# panel_controller_rev_c.net
KiCad netlist of a schematic drawn in EAGLE
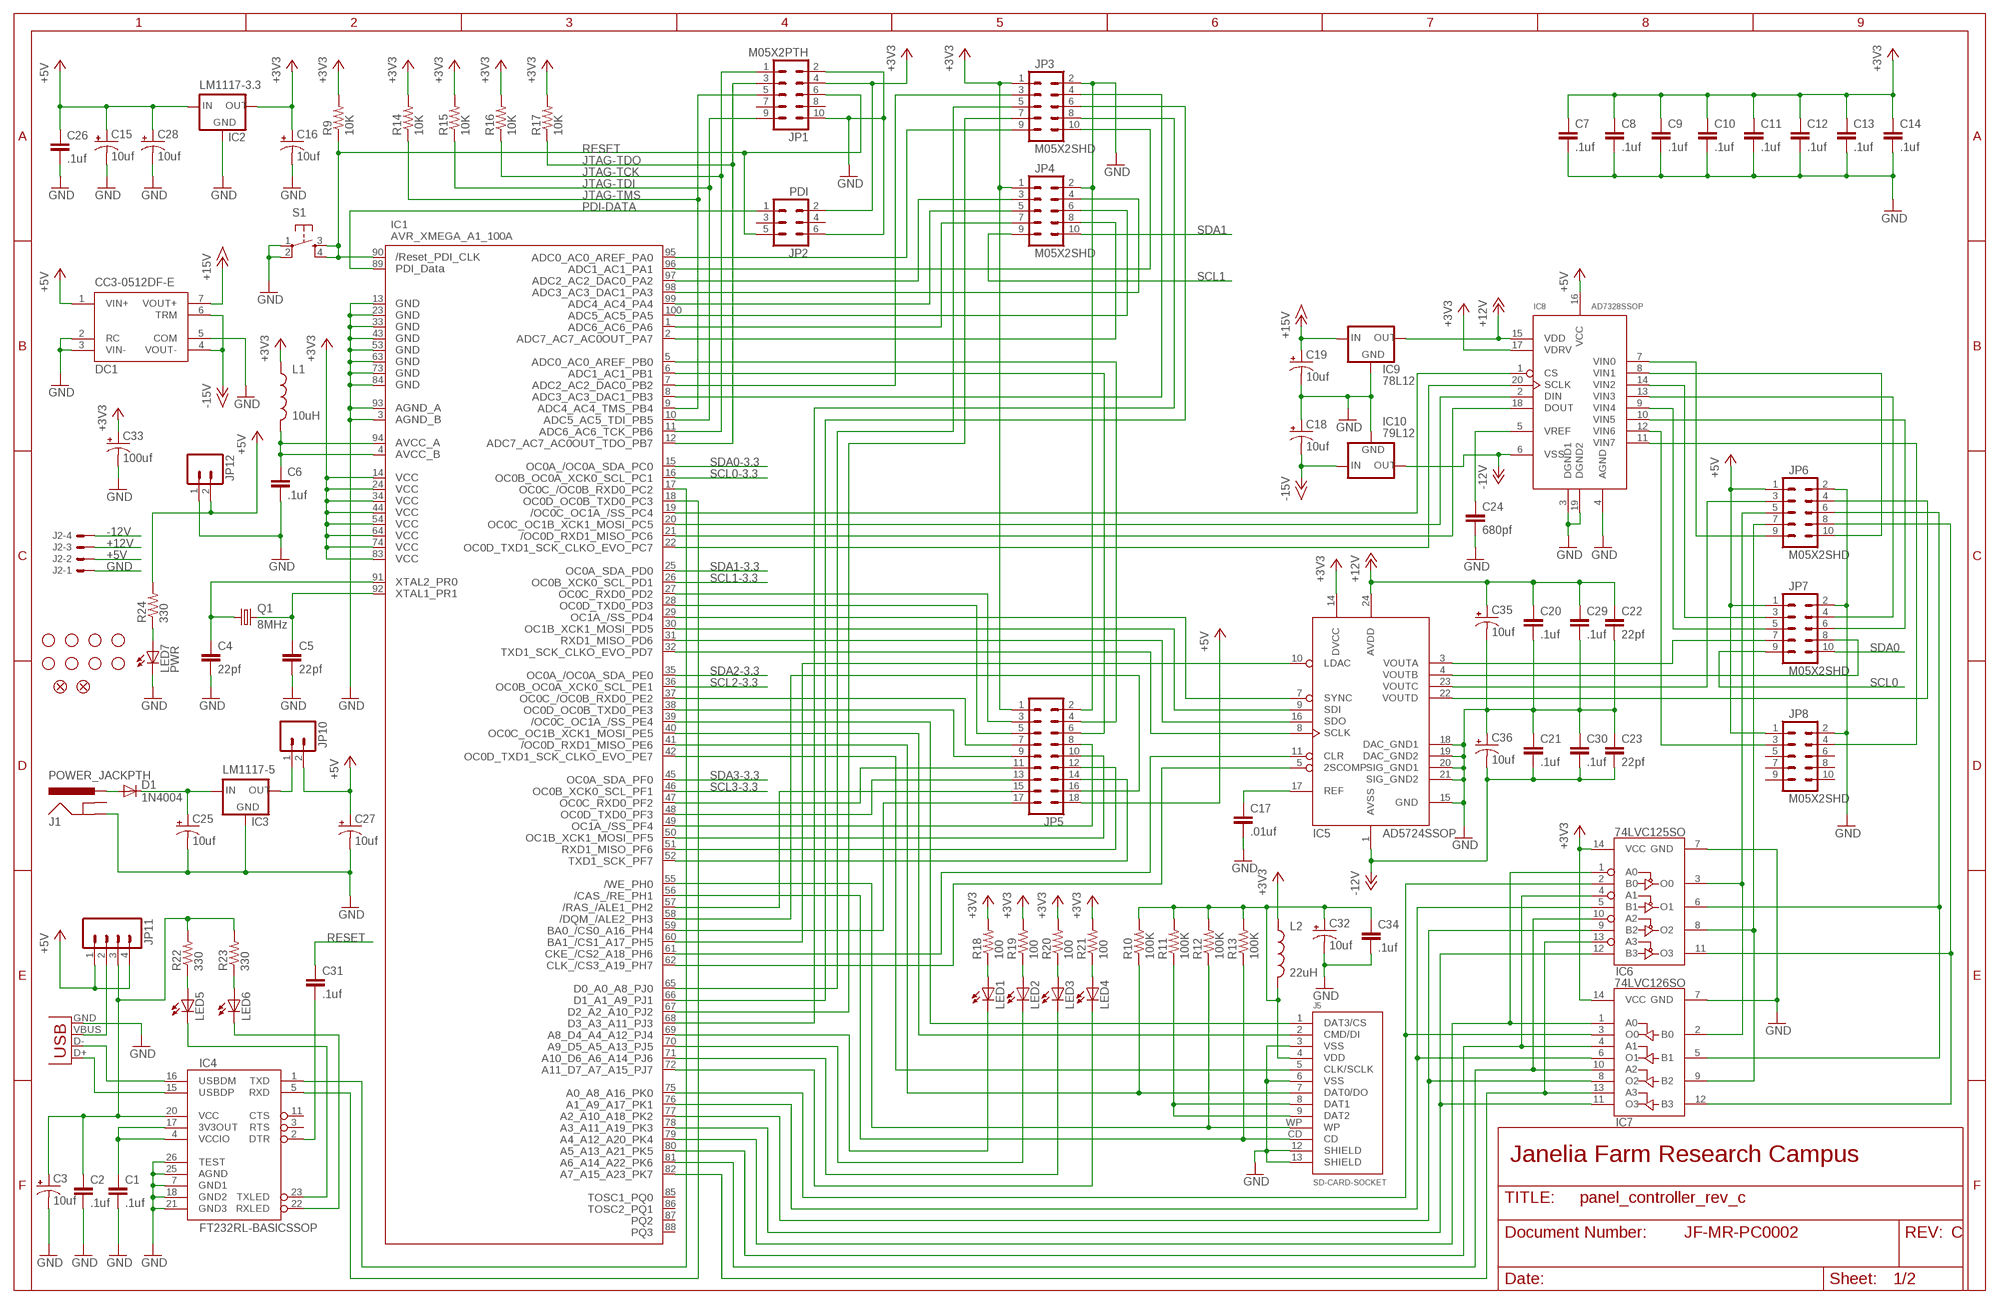
[diagram p0: schematic, sheet 1]
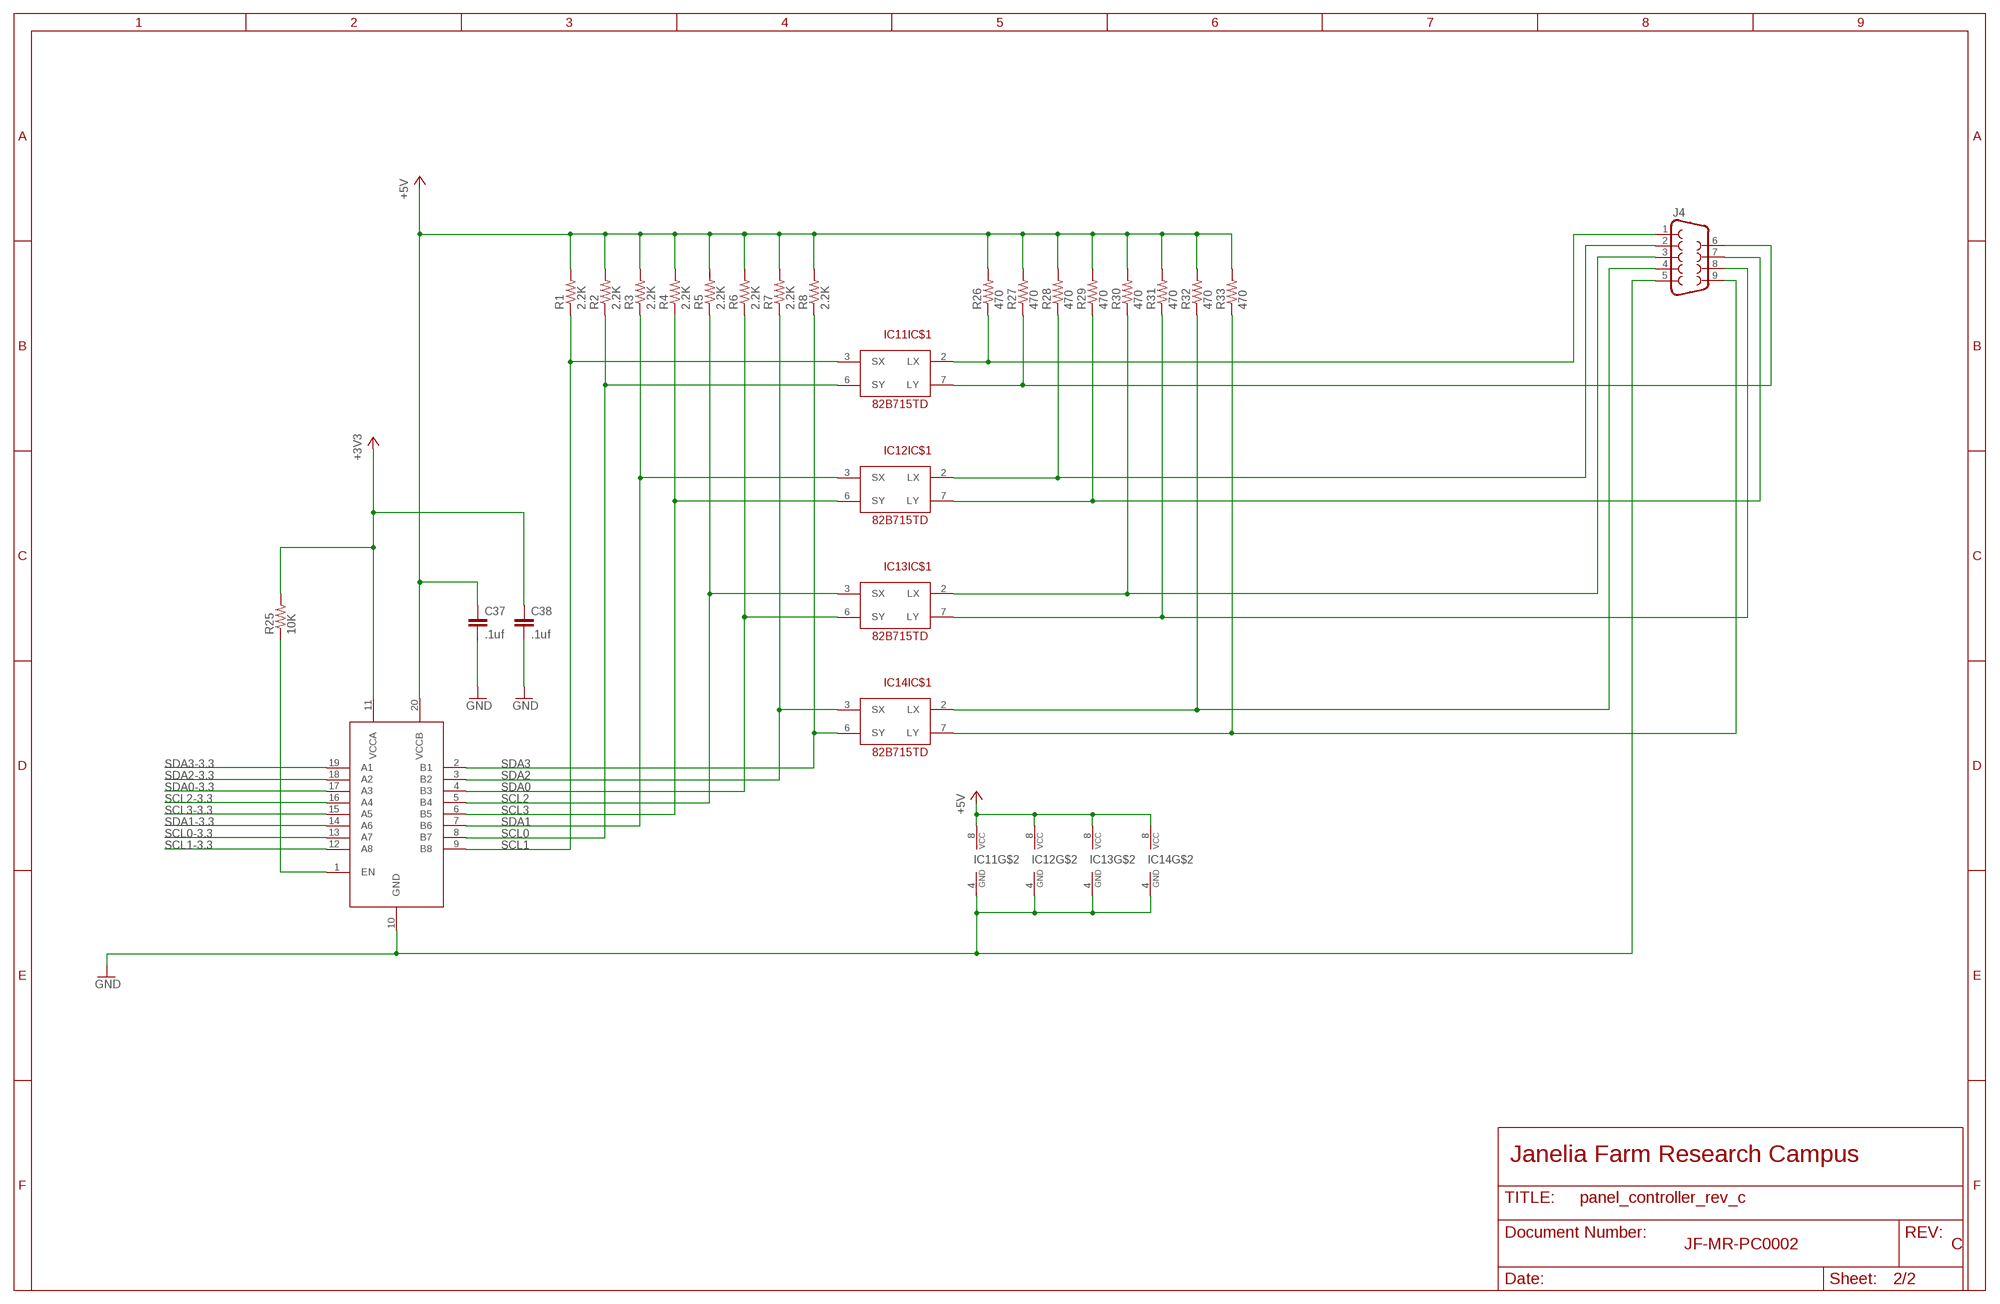
[diagram p1: schematic, sheet 2]

(export (version "E")
  (design (tool "Eeschema 10.0.6"))
  (components
    (comp (ref "C1")
      (value ".1uf")
      (footprint "eagle-import:0603")
      (libsource (lib "eagle-import") (part "CAP0603"))
    )
    (comp (ref "C2")
      (value ".1uf")
      (footprint "eagle-import:0603")
      (libsource (lib "eagle-import") (part "CAP0603"))
    )
    (comp (ref "C3")
      (value "10uf")
      (footprint "eagle-import:EIA3216")
      (libsource (lib "eagle-import") (part "CAP_POL1206"))
    )
    (comp (ref "C4")
      (value "22pf")
      (footprint "eagle-import:0603")
      (libsource (lib "eagle-import") (part "CAP0603"))
    )
    (comp (ref "C5")
      (value "22pf")
      (footprint "eagle-import:0603")
      (libsource (lib "eagle-import") (part "CAP0603"))
    )
    (comp (ref "C6")
      (value ".1uf")
      (footprint "eagle-import:0603")
      (libsource (lib "eagle-import") (part "CAP0603"))
    )
    (comp (ref "C7")
      (value ".1uf")
      (footprint "eagle-import:0603")
      (libsource (lib "eagle-import") (part "CAP0603"))
    )
    (comp (ref "C8")
      (value ".1uf")
      (footprint "eagle-import:0603")
      (libsource (lib "eagle-import") (part "CAP0603"))
    )
    (comp (ref "C9")
      (value ".1uf")
      (footprint "eagle-import:0603")
      (libsource (lib "eagle-import") (part "CAP0603"))
    )
    (comp (ref "C10")
      (value ".1uf")
      (footprint "eagle-import:0603")
      (libsource (lib "eagle-import") (part "CAP0603"))
    )
    (comp (ref "C11")
      (value ".1uf")
      (footprint "eagle-import:0603")
      (libsource (lib "eagle-import") (part "CAP0603"))
    )
    (comp (ref "C12")
      (value ".1uf")
      (footprint "eagle-import:0603")
      (libsource (lib "eagle-import") (part "CAP0603"))
    )
    (comp (ref "C13")
      (value ".1uf")
      (footprint "eagle-import:0603")
      (libsource (lib "eagle-import") (part "CAP0603"))
    )
    (comp (ref "C14")
      (value ".1uf")
      (footprint "eagle-import:0603")
      (libsource (lib "eagle-import") (part "CAP0603"))
    )
    (comp (ref "C15")
      (value "10uf")
      (footprint "eagle-import:EIA3216")
      (libsource (lib "eagle-import") (part "CAP_POL1206"))
    )
    (comp (ref "C16")
      (value "10uf")
      (footprint "eagle-import:EIA3216")
      (libsource (lib "eagle-import") (part "CAP_POL1206"))
    )
    (comp (ref "C17")
      (value ".01uf")
      (footprint "eagle-import:0603")
      (libsource (lib "eagle-import") (part "CAP0603"))
    )
    (comp (ref "C18")
      (value "10uf")
      (footprint "eagle-import:EIA3216")
      (libsource (lib "eagle-import") (part "CAP_POL1206"))
    )
    (comp (ref "C19")
      (value "10uf")
      (footprint "eagle-import:EIA3216")
      (libsource (lib "eagle-import") (part "CAP_POL1206"))
    )
    (comp (ref "C20")
      (value ".1uf")
      (footprint "eagle-import:0603")
      (libsource (lib "eagle-import") (part "CAP0603"))
    )
    (comp (ref "C21")
      (value ".1uf")
      (footprint "eagle-import:0603")
      (libsource (lib "eagle-import") (part "CAP0603"))
    )
    (comp (ref "C22")
      (value "22pf")
      (footprint "eagle-import:0603")
      (libsource (lib "eagle-import") (part "CAP0603"))
    )
    (comp (ref "C23")
      (value "22pf")
      (footprint "eagle-import:0603")
      (libsource (lib "eagle-import") (part "CAP0603"))
    )
    (comp (ref "C24")
      (value "680pf")
      (footprint "eagle-import:0603")
      (libsource (lib "eagle-import") (part "CAP0603"))
    )
    (comp (ref "C25")
      (value "10uf")
      (footprint "eagle-import:EIA3216")
      (libsource (lib "eagle-import") (part "CAP_POL1206"))
    )
    (comp (ref "C26")
      (value ".1uf")
      (footprint "eagle-import:0603")
      (libsource (lib "eagle-import") (part "CAP0603"))
    )
    (comp (ref "C27")
      (value "10uf")
      (footprint "eagle-import:EIA3216")
      (libsource (lib "eagle-import") (part "CAP_POL1206"))
    )
    (comp (ref "C28")
      (value "10uf")
      (footprint "eagle-import:EIA3216")
      (libsource (lib "eagle-import") (part "CAP_POL1206"))
    )
    (comp (ref "C29")
      (value ".1uf")
      (footprint "eagle-import:0603")
      (libsource (lib "eagle-import") (part "CAP0603"))
    )
    (comp (ref "C30")
      (value ".1uf")
      (footprint "eagle-import:0603")
      (libsource (lib "eagle-import") (part "CAP0603"))
    )
    (comp (ref "C31")
      (value ".1uf")
      (footprint "eagle-import:0603")
      (libsource (lib "eagle-import") (part "CAP0603"))
    )
    (comp (ref "C32")
      (value "10uf")
      (footprint "eagle-import:EIA3216")
      (libsource (lib "eagle-import") (part "CAP_POL1206"))
    )
    (comp (ref "C33")
      (value "100uf")
      (footprint "eagle-import:PANASONIC_E")
      (libsource (lib "eagle-import") (part "CAP_POLE"))
    )
    (comp (ref "C34")
      (value ".1uf")
      (footprint "eagle-import:0603")
      (libsource (lib "eagle-import") (part "CAP0603"))
    )
    (comp (ref "C35")
      (value "10uf")
      (footprint "eagle-import:EIA3216")
      (libsource (lib "eagle-import") (part "CAP_POL1206"))
    )
    (comp (ref "C36")
      (value "10uf")
      (footprint "eagle-import:EIA3216")
      (libsource (lib "eagle-import") (part "CAP_POL1206"))
    )
    (comp (ref "D1")
      (value "1N4004")
      (footprint "eagle-import:DO41-10")
      (libsource (lib "eagle-import") (part "1N4004"))
    )
    (comp (ref "DC1")
      (value "CC3-0512DF-E")
      (footprint "eagle-import:CC3-TH")
      (libsource (lib "eagle-import") (part "CC3-0512DF-E"))
    )
    (comp (ref "IC1")
      (value "AVR_XMEGA_A1_100A")
      (footprint "eagle-import:TQFP100")
      (libsource (lib "eagle-import") (part "AVR_XMEGA_A1_100A"))
    )
    (comp (ref "IC2")
      (value "LM1117-3.3")
      (footprint "eagle-import:SOT223")
      (libsource (lib "eagle-import") (part "V_REG_LM1117SOT223"))
    )
    (comp (ref "IC3")
      (value "LM1117-5")
      (footprint "eagle-import:SOT223")
      (libsource (lib "eagle-import") (part "V_REG_LM1117SOT223"))
    )
    (comp (ref "IC4")
      (value "FT232RL-BASICSSOP")
      (footprint "eagle-import:SSOP28DB")
      (libsource (lib "eagle-import") (part "FT232RL-BASICSSOP"))
    )
    (comp (ref "IC5")
      (value "AD5724SSOP")
      (footprint "eagle-import:TSSOP24")
      (libsource (lib "eagle-import") (part "AD5724SSOP"))
    )
    (comp (ref "IC6")
      (value "74LVC125SO")
      (footprint "eagle-import:SO014")
      (libsource (lib "eagle-import") (part "74LVC125SO"))
    )
    (comp (ref "IC7")
      (value "74LVC126SO")
      (footprint "eagle-import:SO014")
      (libsource (lib "eagle-import") (part "74LVC126SO"))
    )
    (comp (ref "IC8")
      (value "AD7328SSOP")
      (footprint "eagle-import:TSSOP20")
      (libsource (lib "eagle-import") (part "AD7328SSOP"))
    )
    (comp (ref "IC9")
      (value "78L12")
      (footprint "eagle-import:SOT89")
      (libsource (lib "eagle-import") (part "78LXXSOT89"))
    )
    (comp (ref "IC10")
      (value "79L12")
      (footprint "eagle-import:SOT89")
      (libsource (lib "eagle-import") (part "79LXXSOT89"))
    )
    (comp (ref "J1")
      (value "POWER_JACKPTH")
      (footprint "eagle-import:POWER_JACK_PTH")
      (libsource (lib "eagle-import") (part "POWER_JACKPTH"))
    )
    (comp (ref "J2")
      (value "KK-156-4")
      (footprint "eagle-import:KK-156-4")
      (libsource (lib "eagle-import") (part "KK-156-4"))
    )
    (comp (ref "J3")
      (value "USBPTH")
      (footprint "eagle-import:USB-B-PTH")
      (libsource (lib "eagle-import") (part "USBPTH"))
    )
    (comp (ref "J5")
      (value "SD-CARD-SOCKET")
      (footprint "eagle-import:SD-MMC_SOCKET-3M")
      (libsource (lib "eagle-import") (part "SD-CARD-SOCKET"))
    )
    (comp (ref "JP1")
      (value "M05X2PTH")
      (footprint "eagle-import:MA05-2")
      (libsource (lib "eagle-import") (part "MA05-2"))
    )
    (comp (ref "JP2")
      (value "PDI")
      (footprint "eagle-import:MA03-2")
      (libsource (lib "eagle-import") (part "MA03-2"))
    )
    (comp (ref "JP3")
      (value "M05X2SHD")
      (footprint "eagle-import:2X5-SHROUDED")
      (libsource (lib "eagle-import") (part "M05X2SHD"))
    )
    (comp (ref "JP4")
      (value "M05X2SHD")
      (footprint "eagle-import:2X5-SHROUDED")
      (libsource (lib "eagle-import") (part "M05X2SHD"))
    )
    (comp (ref "JP5")
      (value "MA09-2")
      (footprint "eagle-import:MA09-2")
      (libsource (lib "eagle-import") (part "MA09-2"))
    )
    (comp (ref "JP6")
      (value "M05X2SHD")
      (footprint "eagle-import:2X5-SHROUDED")
      (libsource (lib "eagle-import") (part "M05X2SHD"))
    )
    (comp (ref "JP7")
      (value "M05X2SHD")
      (footprint "eagle-import:2X5-SHROUDED")
      (libsource (lib "eagle-import") (part "M05X2SHD"))
    )
    (comp (ref "JP8")
      (value "M05X2SHD")
      (footprint "eagle-import:2X5-SHROUDED")
      (libsource (lib "eagle-import") (part "M05X2SHD"))
    )
    (comp (ref "JP10")
      (value "M02PTH")
      (footprint "eagle-import:1X02")
      (libsource (lib "eagle-import") (part "M02PTH"))
    )
    (comp (ref "JP11")
      (value "M04PTH")
      (footprint "eagle-import:1X04")
      (libsource (lib "eagle-import") (part "M04PTH"))
    )
    (comp (ref "JP12")
      (value "M02PTH")
      (footprint "eagle-import:1X02")
      (libsource (lib "eagle-import") (part "M02PTH"))
    )
    (comp (ref "L1")
      (value "10uH")
      (footprint "eagle-import:0805")
      (libsource (lib "eagle-import") (part "INDUCTOR0805"))
    )
    (comp (ref "L2")
      (value "22uH")
      (footprint "eagle-import:0805")
      (libsource (lib "eagle-import") (part "INDUCTOR0805"))
    )
    (comp (ref "LED1")
      (value "LED3MM")
      (footprint "eagle-import:LED3MM")
      (libsource (lib "eagle-import") (part "LED3MM"))
    )
    (comp (ref "LED2")
      (value "LED3MM")
      (footprint "eagle-import:LED3MM")
      (libsource (lib "eagle-import") (part "LED3MM"))
    )
    (comp (ref "LED3")
      (value "LED3MM")
      (footprint "eagle-import:LED3MM")
      (libsource (lib "eagle-import") (part "LED3MM"))
    )
    (comp (ref "LED4")
      (value "LED3MM")
      (footprint "eagle-import:LED3MM")
      (libsource (lib "eagle-import") (part "LED3MM"))
    )
    (comp (ref "LED5")
      (value "LED3MM")
      (footprint "eagle-import:LED3MM")
      (libsource (lib "eagle-import") (part "LED3MM"))
    )
    (comp (ref "LED6")
      (value "LED3MM")
      (footprint "eagle-import:LED3MM")
      (libsource (lib "eagle-import") (part "LED3MM"))
    )
    (comp (ref "LED7")
      (value "PWR")
      (footprint "eagle-import:LED3MM")
      (libsource (lib "eagle-import") (part "LED3MM"))
    )
    (comp (ref "Q1")
      (value "8MHz")
      (footprint "eagle-import:HC49UP")
      (libsource (lib "eagle-import") (part "CRYSTALSMD"))
    )
    (comp (ref "R9")
      (value "10K")
      (footprint "eagle-import:0603")
      (libsource (lib "eagle-import") (part "RESISTOR0603"))
    )
    (comp (ref "R10")
      (value "100K")
      (footprint "eagle-import:0603")
      (libsource (lib "eagle-import") (part "RESISTOR0603"))
    )
    (comp (ref "R11")
      (value "100K")
      (footprint "eagle-import:0603")
      (libsource (lib "eagle-import") (part "RESISTOR0603"))
    )
    (comp (ref "R12")
      (value "100K")
      (footprint "eagle-import:0603")
      (libsource (lib "eagle-import") (part "RESISTOR0603"))
    )
    (comp (ref "R13")
      (value "100K")
      (footprint "eagle-import:0603")
      (libsource (lib "eagle-import") (part "RESISTOR0603"))
    )
    (comp (ref "R14")
      (value "10K")
      (footprint "eagle-import:0603")
      (libsource (lib "eagle-import") (part "RESISTOR0603"))
    )
    (comp (ref "R15")
      (value "10K")
      (footprint "eagle-import:0603")
      (libsource (lib "eagle-import") (part "RESISTOR0603"))
    )
    (comp (ref "R16")
      (value "10K")
      (footprint "eagle-import:0603")
      (libsource (lib "eagle-import") (part "RESISTOR0603"))
    )
    (comp (ref "R17")
      (value "10K")
      (footprint "eagle-import:0603")
      (libsource (lib "eagle-import") (part "RESISTOR0603"))
    )
    (comp (ref "R18")
      (value "100")
      (footprint "eagle-import:0603")
      (libsource (lib "eagle-import") (part "RESISTOR0603"))
    )
    (comp (ref "R19")
      (value "100")
      (footprint "eagle-import:0603")
      (libsource (lib "eagle-import") (part "RESISTOR0603"))
    )
    (comp (ref "R20")
      (value "100")
      (footprint "eagle-import:0603")
      (libsource (lib "eagle-import") (part "RESISTOR0603"))
    )
    (comp (ref "R21")
      (value "100")
      (footprint "eagle-import:0603")
      (libsource (lib "eagle-import") (part "RESISTOR0603"))
    )
    (comp (ref "R22")
      (value "330")
      (footprint "eagle-import:0603")
      (libsource (lib "eagle-import") (part "RESISTOR0603"))
    )
    (comp (ref "R23")
      (value "330")
      (footprint "eagle-import:0603")
      (libsource (lib "eagle-import") (part "RESISTOR0603"))
    )
    (comp (ref "R24")
      (value "330")
      (footprint "eagle-import:0603")
      (libsource (lib "eagle-import") (part "RESISTOR0603"))
    )
    (comp (ref "S1")
      (value "TAC_SWITCHB3S-1000")
      (footprint "eagle-import:OMRON")
      (libsource (lib "eagle-import") (part "TAC_SWITCHB3S-1000"))
    )
    (comp (ref "U$1")
      (value "FIDUCIAL1X2")
      (footprint "eagle-import:FIDUCIAL-1X2")
      (libsource (lib "eagle-import") (part "FIDUCIAL1X2"))
    )
    (comp (ref "U$2")
      (value "FIDUCIAL1X2")
      (footprint "eagle-import:FIDUCIAL-1X2")
      (libsource (lib "eagle-import") (part "FIDUCIAL1X2"))
    )
    (comp (ref "U$3")
      (value "STAND-OFF")
      (footprint "eagle-import:STAND-OFF")
      (libsource (lib "eagle-import") (part "STAND-OFF"))
    )
    (comp (ref "U$4")
      (value "STAND-OFF")
      (footprint "eagle-import:STAND-OFF")
      (libsource (lib "eagle-import") (part "STAND-OFF"))
    )
    (comp (ref "U$5")
      (value "STAND-OFF")
      (footprint "eagle-import:STAND-OFF")
      (libsource (lib "eagle-import") (part "STAND-OFF"))
    )
    (comp (ref "U$6")
      (value "STAND-OFF")
      (footprint "eagle-import:STAND-OFF")
      (libsource (lib "eagle-import") (part "STAND-OFF"))
    )
    (comp (ref "U$7")
      (value "STAND-OFF")
      (footprint "eagle-import:STAND-OFF")
      (libsource (lib "eagle-import") (part "STAND-OFF"))
    )
    (comp (ref "U$8")
      (value "STAND-OFF")
      (footprint "eagle-import:STAND-OFF")
      (libsource (lib "eagle-import") (part "STAND-OFF"))
    )
    (comp (ref "U$9")
      (value "STAND-OFF")
      (footprint "eagle-import:STAND-OFF")
      (libsource (lib "eagle-import") (part "STAND-OFF"))
    )
    (comp (ref "U$10")
      (value "STAND-OFF")
      (footprint "eagle-import:STAND-OFF")
      (libsource (lib "eagle-import") (part "STAND-OFF"))
    )
    (comp (ref "C37")
      (value ".1uf")
      (footprint "eagle-import:0603")
      (libsource (lib "eagle-import") (part "CAP0603"))
    )
    (comp (ref "C38")
      (value ".1uf")
      (footprint "eagle-import:0603")
      (libsource (lib "eagle-import") (part "CAP0603"))
    )
    (comp (ref "IC11")
      (value "82B715TD")
      (footprint "eagle-import:SO08")
      (libsource (lib "eagle-import") (part "82B715TD"))
    )
    (comp (ref "IC12")
      (value "82B715TD")
      (footprint "eagle-import:SO08")
      (libsource (lib "eagle-import") (part "82B715TD"))
    )
    (comp (ref "IC13")
      (value "82B715TD")
      (footprint "eagle-import:SO08")
      (libsource (lib "eagle-import") (part "82B715TD"))
    )
    (comp (ref "IC14")
      (value "82B715TD")
      (footprint "eagle-import:SO08")
      (libsource (lib "eagle-import") (part "82B715TD"))
    )
    (comp (ref "IC15")
      (value "PCA9519")
      (footprint "eagle-import:TSSOP20")
      (libsource (lib "eagle-import") (part "PCA9519"))
    )
    (comp (ref "J4")
      (value "DB9")
      (footprint "eagle-import:DB9")
      (libsource (lib "eagle-import") (part "DB9"))
    )
    (comp (ref "R1")
      (value "2.2K")
      (footprint "eagle-import:0603")
      (libsource (lib "eagle-import") (part "RESISTOR0603"))
    )
    (comp (ref "R2")
      (value "2.2K")
      (footprint "eagle-import:0603")
      (libsource (lib "eagle-import") (part "RESISTOR0603"))
    )
    (comp (ref "R3")
      (value "2.2K")
      (footprint "eagle-import:0603")
      (libsource (lib "eagle-import") (part "RESISTOR0603"))
    )
    (comp (ref "R4")
      (value "2.2K")
      (footprint "eagle-import:0603")
      (libsource (lib "eagle-import") (part "RESISTOR0603"))
    )
    (comp (ref "R5")
      (value "2.2K")
      (footprint "eagle-import:0603")
      (libsource (lib "eagle-import") (part "RESISTOR0603"))
    )
    (comp (ref "R6")
      (value "2.2K")
      (footprint "eagle-import:0603")
      (libsource (lib "eagle-import") (part "RESISTOR0603"))
    )
    (comp (ref "R7")
      (value "2.2K")
      (footprint "eagle-import:0603")
      (libsource (lib "eagle-import") (part "RESISTOR0603"))
    )
    (comp (ref "R8")
      (value "2.2K")
      (footprint "eagle-import:0603")
      (libsource (lib "eagle-import") (part "RESISTOR0603"))
    )
    (comp (ref "R25")
      (value "10K")
      (footprint "eagle-import:0603")
      (libsource (lib "eagle-import") (part "RESISTOR0603"))
    )
    (comp (ref "R26")
      (value "470")
      (footprint "eagle-import:0603")
      (libsource (lib "eagle-import") (part "RESISTOR0603"))
    )
    (comp (ref "R27")
      (value "470")
      (footprint "eagle-import:0603")
      (libsource (lib "eagle-import") (part "RESISTOR0603"))
    )
    (comp (ref "R28")
      (value "470")
      (footprint "eagle-import:0603")
      (libsource (lib "eagle-import") (part "RESISTOR0603"))
    )
    (comp (ref "R29")
      (value "470")
      (footprint "eagle-import:0603")
      (libsource (lib "eagle-import") (part "RESISTOR0603"))
    )
    (comp (ref "R30")
      (value "470")
      (footprint "eagle-import:0603")
      (libsource (lib "eagle-import") (part "RESISTOR0603"))
    )
    (comp (ref "R31")
      (value "470")
      (footprint "eagle-import:0603")
      (libsource (lib "eagle-import") (part "RESISTOR0603"))
    )
    (comp (ref "R32")
      (value "470")
      (footprint "eagle-import:0603")
      (libsource (lib "eagle-import") (part "RESISTOR0603"))
    )
    (comp (ref "R33")
      (value "470")
      (footprint "eagle-import:0603")
      (libsource (lib "eagle-import") (part "RESISTOR0603"))
    )
  )
  (nets
    (net (code "1") (name "+3V3") (class "Default")
      (node (ref "C10") (pin "1") (pinfunction "1_1") (pintype "passive"))
      (node (ref "C11") (pin "1") (pinfunction "1_1") (pintype "passive"))
      (node (ref "C12") (pin "1") (pinfunction "1_1") (pintype "passive"))
      (node (ref "C13") (pin "1") (pinfunction "1_1") (pintype "passive"))
      (node (ref "C14") (pin "1") (pinfunction "1_1") (pintype "passive"))
      (node (ref "C16") (pin "A") (pinfunction "+_A") (pintype "passive"))
      (node (ref "C33") (pin "+") (pinfunction "+_+") (pintype "passive"))
      (node (ref "C38") (pin "1") (pinfunction "1_1") (pintype "passive"))
      (node (ref "C7") (pin "1") (pinfunction "1_1") (pintype "passive"))
      (node (ref "C8") (pin "1") (pinfunction "1_1") (pintype "passive"))
      (node (ref "C9") (pin "1") (pinfunction "1_1") (pintype "passive"))
      (node (ref "IC1") (pin "14") (pinfunction "VCC1_14") (pintype "bidirectional"))
      (node (ref "IC1") (pin "24") (pinfunction "VCC2_24") (pintype "bidirectional"))
      (node (ref "IC1") (pin "34") (pinfunction "VCC3_34") (pintype "bidirectional"))
      (node (ref "IC1") (pin "44") (pinfunction "VCC4_44") (pintype "bidirectional"))
      (node (ref "IC1") (pin "54") (pinfunction "VCC5_54") (pintype "bidirectional"))
      (node (ref "IC1") (pin "64") (pinfunction "VCC6_64") (pintype "bidirectional"))
      (node (ref "IC1") (pin "74") (pinfunction "VCC7_74") (pintype "bidirectional"))
      (node (ref "IC1") (pin "83") (pinfunction "VCC8_83") (pintype "bidirectional"))
      (node (ref "IC15") (pin "11") (pinfunction "VCCA_11") (pintype "power_in"))
      (node (ref "IC2") (pin "2") (pinfunction "OUT_2") (pintype "power_in"))
      (node (ref "IC5") (pin "14") (pinfunction "DVCC_14") (pintype "power_in"))
      (node (ref "IC6") (pin "14") (pinfunction "VCC_14") (pintype "power_in"))
      (node (ref "IC7") (pin "14") (pinfunction "VCC_14") (pintype "power_in"))
      (node (ref "IC8") (pin "17") (pinfunction "VDRV_17") (pintype "power_in"))
      (node (ref "JP1") (pin "4") (pinfunction "4_4") (pintype "passive"))
      (node (ref "JP2") (pin "2") (pinfunction "2_2") (pintype "passive"))
      (node (ref "JP3") (pin "1") (pinfunction "1_1") (pintype "passive"))
      (node (ref "JP4") (pin "1") (pinfunction "1_1") (pintype "passive"))
      (node (ref "JP5") (pin "1") (pinfunction "1_1") (pintype "passive"))
      (node (ref "L1") (pin "1") (pinfunction "1_1") (pintype "passive"))
      (node (ref "L2") (pin "1") (pinfunction "1_1") (pintype "passive"))
      (node (ref "R14") (pin "2") (pinfunction "2_2") (pintype "passive"))
      (node (ref "R15") (pin "2") (pinfunction "2_2") (pintype "passive"))
      (node (ref "R16") (pin "2") (pinfunction "2_2") (pintype "passive"))
      (node (ref "R17") (pin "2") (pinfunction "2_2") (pintype "passive"))
      (node (ref "R18") (pin "2") (pinfunction "2_2") (pintype "passive"))
      (node (ref "R19") (pin "2") (pinfunction "2_2") (pintype "passive"))
      (node (ref "R20") (pin "2") (pinfunction "2_2") (pintype "passive"))
      (node (ref "R21") (pin "2") (pinfunction "2_2") (pintype "passive"))
      (node (ref "R25") (pin "2") (pinfunction "2_2") (pintype "passive"))
      (node (ref "R9") (pin "2") (pinfunction "2_2") (pintype "passive"))
    )
    (net (code "2") (name "+5V") (class "Default")
      (node (ref "C15") (pin "A") (pinfunction "+_A") (pintype "passive"))
      (node (ref "C26") (pin "1") (pinfunction "1_1") (pintype "passive"))
      (node (ref "C27") (pin "A") (pinfunction "+_A") (pintype "passive"))
      (node (ref "C28") (pin "A") (pinfunction "+_A") (pintype "passive"))
      (node (ref "C37") (pin "1") (pinfunction "1_1") (pintype "passive"))
      (node (ref "DC1") (pin "1") (pinfunction "VIN+_1") (pintype "power_in"))
      (node (ref "IC11") (pin "8") (pinfunction "VCC_8") (pintype "power_in"))
      (node (ref "IC12") (pin "8") (pinfunction "VCC_8") (pintype "power_in"))
      (node (ref "IC13") (pin "8") (pinfunction "VCC_8") (pintype "power_in"))
      (node (ref "IC14") (pin "8") (pinfunction "VCC_8") (pintype "power_in"))
      (node (ref "IC15") (pin "20") (pinfunction "VCCB_20") (pintype "power_in"))
      (node (ref "IC2") (pin "3") (pinfunction "IN_3") (pintype "power_in"))
      (node (ref "IC8") (pin "16") (pinfunction "VCC_16") (pintype "power_in"))
      (node (ref "J2") (pin "2") (pinfunction "S_2") (pintype "passive"))
      (node (ref "JP10") (pin "2") (pinfunction "2_2") (pintype "passive"))
      (node (ref "JP11") (pin "1") (pinfunction "1_1") (pintype "passive"))
      (node (ref "JP11") (pin "4") (pinfunction "4_4") (pintype "passive"))
      (node (ref "JP12") (pin "2") (pinfunction "2_2") (pintype "passive"))
      (node (ref "JP5") (pin "18") (pinfunction "18_18") (pintype "passive"))
      (node (ref "JP6") (pin "1") (pinfunction "1_1") (pintype "passive"))
      (node (ref "JP7") (pin "1") (pinfunction "1_1") (pintype "passive"))
      (node (ref "JP8") (pin "1") (pinfunction "1_1") (pintype "passive"))
      (node (ref "R1") (pin "2") (pinfunction "2_2") (pintype "passive"))
      (node (ref "R2") (pin "2") (pinfunction "2_2") (pintype "passive"))
      (node (ref "R24") (pin "2") (pinfunction "2_2") (pintype "passive"))
      (node (ref "R26") (pin "2") (pinfunction "2_2") (pintype "passive"))
      (node (ref "R27") (pin "2") (pinfunction "2_2") (pintype "passive"))
      (node (ref "R28") (pin "2") (pinfunction "2_2") (pintype "passive"))
      (node (ref "R29") (pin "2") (pinfunction "2_2") (pintype "passive"))
      (node (ref "R3") (pin "2") (pinfunction "2_2") (pintype "passive"))
      (node (ref "R30") (pin "2") (pinfunction "2_2") (pintype "passive"))
      (node (ref "R31") (pin "2") (pinfunction "2_2") (pintype "passive"))
      (node (ref "R32") (pin "2") (pinfunction "2_2") (pintype "passive"))
      (node (ref "R33") (pin "2") (pinfunction "2_2") (pintype "passive"))
      (node (ref "R4") (pin "2") (pinfunction "2_2") (pintype "passive"))
      (node (ref "R5") (pin "2") (pinfunction "2_2") (pintype "passive"))
      (node (ref "R6") (pin "2") (pinfunction "2_2") (pintype "passive"))
      (node (ref "R7") (pin "2") (pinfunction "2_2") (pintype "passive"))
      (node (ref "R8") (pin "2") (pinfunction "2_2") (pintype "passive"))
    )
    (net (code "3") (name "+12V") (class "Default")
      (node (ref "C20") (pin "1") (pinfunction "1_1") (pintype "passive"))
      (node (ref "C22") (pin "1") (pinfunction "1_1") (pintype "passive"))
      (node (ref "C29") (pin "1") (pinfunction "1_1") (pintype "passive"))
      (node (ref "C35") (pin "A") (pinfunction "+_A") (pintype "passive"))
      (node (ref "IC5") (pin "24") (pinfunction "AVDD_24") (pintype "power_in"))
      (node (ref "IC8") (pin "15") (pinfunction "VDD_15") (pintype "power_in"))
      (node (ref "IC9") (pin "1") (pinfunction "OUT_1") (pintype "passive"))
      (node (ref "J2") (pin "3") (pinfunction "S_3") (pintype "passive"))
    )
    (net (code "4") (name "+15V") (class "Default")
      (node (ref "C19") (pin "A") (pinfunction "+_A") (pintype "passive"))
      (node (ref "DC1") (pin "7") (pinfunction "VOUT+_7") (pintype "power_in"))
      (node (ref "IC9") (pin "3") (pinfunction "IN_3") (pintype "input"))
    )
    (net (code "5") (name "-12V") (class "Default")
      (node (ref "C21") (pin "2") (pinfunction "2_2") (pintype "passive"))
      (node (ref "C23") (pin "2") (pinfunction "2_2") (pintype "passive"))
      (node (ref "C30") (pin "2") (pinfunction "2_2") (pintype "passive"))
      (node (ref "C36") (pin "C") (pinfunction "-_C") (pintype "passive"))
      (node (ref "IC10") (pin "3") (pinfunction "OUT_3") (pintype "passive"))
      (node (ref "IC5") (pin "1") (pinfunction "AVSS_1") (pintype "power_in"))
      (node (ref "IC8") (pin "6") (pinfunction "VSS_6") (pintype "power_in"))
      (node (ref "J2") (pin "4") (pinfunction "S_4") (pintype "passive"))
    )
    (net (code "6") (name "-15V") (class "Default")
      (node (ref "C18") (pin "C") (pinfunction "-_C") (pintype "passive"))
      (node (ref "DC1") (pin "4") (pinfunction "VOUT-_4") (pintype "power_in"))
      (node (ref "DC1") (pin "6") (pinfunction "TRM_6") (pintype "input"))
      (node (ref "IC10") (pin "2") (pinfunction "IN_2") (pintype "input"))
    )
    (net (code "7") (name "GND") (class "Default")
      (node (ref "C1") (pin "2") (pinfunction "2_2") (pintype "passive"))
      (node (ref "C10") (pin "2") (pinfunction "2_2") (pintype "passive"))
      (node (ref "C11") (pin "2") (pinfunction "2_2") (pintype "passive"))
      (node (ref "C12") (pin "2") (pinfunction "2_2") (pintype "passive"))
      (node (ref "C13") (pin "2") (pinfunction "2_2") (pintype "passive"))
      (node (ref "C14") (pin "2") (pinfunction "2_2") (pintype "passive"))
      (node (ref "C15") (pin "C") (pinfunction "-_C") (pintype "passive"))
      (node (ref "C16") (pin "C") (pinfunction "-_C") (pintype "passive"))
      (node (ref "C17") (pin "2") (pinfunction "2_2") (pintype "passive"))
      (node (ref "C18") (pin "A") (pinfunction "+_A") (pintype "passive"))
      (node (ref "C19") (pin "C") (pinfunction "-_C") (pintype "passive"))
      (node (ref "C2") (pin "2") (pinfunction "2_2") (pintype "passive"))
      (node (ref "C20") (pin "2") (pinfunction "2_2") (pintype "passive"))
      (node (ref "C21") (pin "1") (pinfunction "1_1") (pintype "passive"))
      (node (ref "C22") (pin "2") (pinfunction "2_2") (pintype "passive"))
      (node (ref "C23") (pin "1") (pinfunction "1_1") (pintype "passive"))
      (node (ref "C24") (pin "2") (pinfunction "2_2") (pintype "passive"))
      (node (ref "C25") (pin "C") (pinfunction "-_C") (pintype "passive"))
      (node (ref "C26") (pin "2") (pinfunction "2_2") (pintype "passive"))
      (node (ref "C27") (pin "C") (pinfunction "-_C") (pintype "passive"))
      (node (ref "C28") (pin "C") (pinfunction "-_C") (pintype "passive"))
      (node (ref "C29") (pin "2") (pinfunction "2_2") (pintype "passive"))
      (node (ref "C3") (pin "C") (pinfunction "-_C") (pintype "passive"))
      (node (ref "C30") (pin "1") (pinfunction "1_1") (pintype "passive"))
      (node (ref "C32") (pin "C") (pinfunction "-_C") (pintype "passive"))
      (node (ref "C33") (pin "-") (pinfunction "-_-") (pintype "passive"))
      (node (ref "C34") (pin "2") (pinfunction "2_2") (pintype "passive"))
      (node (ref "C35") (pin "C") (pinfunction "-_C") (pintype "passive"))
      (node (ref "C36") (pin "A") (pinfunction "+_A") (pintype "passive"))
      (node (ref "C37") (pin "2") (pinfunction "2_2") (pintype "passive"))
      (node (ref "C38") (pin "2") (pinfunction "2_2") (pintype "passive"))
      (node (ref "C4") (pin "2") (pinfunction "2_2") (pintype "passive"))
      (node (ref "C5") (pin "2") (pinfunction "2_2") (pintype "passive"))
      (node (ref "C6") (pin "2") (pinfunction "2_2") (pintype "passive"))
      (node (ref "C7") (pin "2") (pinfunction "2_2") (pintype "passive"))
      (node (ref "C8") (pin "2") (pinfunction "2_2") (pintype "passive"))
      (node (ref "C9") (pin "2") (pinfunction "2_2") (pintype "passive"))
      (node (ref "DC1") (pin "2") (pinfunction "RC_2") (pintype "input"))
      (node (ref "DC1") (pin "3") (pinfunction "VIN-_3") (pintype "power_in"))
      (node (ref "DC1") (pin "5") (pinfunction "COM_5") (pintype "power_in"))
      (node (ref "IC1") (pin "13") (pinfunction "GND1_13") (pintype "bidirectional"))
      (node (ref "IC1") (pin "23") (pinfunction "GND2_23") (pintype "bidirectional"))
      (node (ref "IC1") (pin "3") (pinfunction "AGND_B_3") (pintype "bidirectional"))
      (node (ref "IC1") (pin "33") (pinfunction "GND3_33") (pintype "bidirectional"))
      (node (ref "IC1") (pin "43") (pinfunction "GND4_43") (pintype "bidirectional"))
      (node (ref "IC1") (pin "53") (pinfunction "GND5_53") (pintype "bidirectional"))
      (node (ref "IC1") (pin "63") (pinfunction "GND6_63") (pintype "bidirectional"))
      (node (ref "IC1") (pin "73") (pinfunction "GND7_73") (pintype "bidirectional"))
      (node (ref "IC1") (pin "84") (pinfunction "GND8_84") (pintype "bidirectional"))
      (node (ref "IC1") (pin "93") (pinfunction "AGND_A_93") (pintype "bidirectional"))
      (node (ref "IC10") (pin "1") (pinfunction "GND_1") (pintype "input"))
      (node (ref "IC11") (pin "4") (pinfunction "GND_4") (pintype "power_in"))
      (node (ref "IC12") (pin "4") (pinfunction "GND_4") (pintype "power_in"))
      (node (ref "IC13") (pin "4") (pinfunction "GND_4") (pintype "power_in"))
      (node (ref "IC14") (pin "4") (pinfunction "GND_4") (pintype "power_in"))
      (node (ref "IC15") (pin "10") (pinfunction "GND_10") (pintype "power_in"))
      (node (ref "IC2") (pin "1") (pinfunction "GND_1") (pintype "power_in"))
      (node (ref "IC3") (pin "1") (pinfunction "GND_1") (pintype "power_in"))
      (node (ref "IC4") (pin "18") (pinfunction "GND2_18") (pintype "power_in"))
      (node (ref "IC4") (pin "21") (pinfunction "GND3_21") (pintype "power_in"))
      (node (ref "IC4") (pin "25") (pinfunction "AGND_25") (pintype "power_in"))
      (node (ref "IC4") (pin "26") (pinfunction "TEST_26") (pintype "input"))
      (node (ref "IC4") (pin "7") (pinfunction "GND1_7") (pintype "power_in"))
      (node (ref "IC5") (pin "15") (pinfunction "GND_15") (pintype "power_in"))
      (node (ref "IC5") (pin "18") (pinfunction "DAC_GND1_18") (pintype "power_in"))
      (node (ref "IC5") (pin "19") (pinfunction "DAC_GND2_19") (pintype "power_in"))
      (node (ref "IC5") (pin "20") (pinfunction "SIG_GND1_20") (pintype "power_in"))
      (node (ref "IC5") (pin "21") (pinfunction "SIG_GND2_21") (pintype "power_in"))
      (node (ref "IC6") (pin "7") (pinfunction "GND_7") (pintype "power_in"))
      (node (ref "IC7") (pin "7") (pinfunction "GND_7") (pintype "power_in"))
      (node (ref "IC8") (pin "19") (pinfunction "DGND2_19") (pintype "power_in"))
      (node (ref "IC8") (pin "3") (pinfunction "DGND1_3") (pintype "power_in"))
      (node (ref "IC8") (pin "4") (pinfunction "AGND_4") (pintype "power_in"))
      (node (ref "IC9") (pin "2") (pinfunction "GND_2") (pintype "input"))
      (node (ref "J1") (pin "GND") (pinfunction "GND_GND") (pintype "bidirectional"))
      (node (ref "J2") (pin "1") (pinfunction "S_1") (pintype "passive"))
      (node (ref "J3") (pin "GND") (pinfunction "GND_GND") (pintype "bidirectional"))
      (node (ref "J4") (pin "5") (pinfunction "5_5") (pintype "passive"))
      (node (ref "J5") (pin "12") (pinfunction "SHIELD_12") (pintype "bidirectional"))
      (node (ref "J5") (pin "13") (pinfunction "SHIELD_13") (pintype "bidirectional"))
      (node (ref "J5") (pin "3") (pinfunction "VSS_3") (pintype "bidirectional"))
      (node (ref "J5") (pin "6") (pinfunction "VSS_6") (pintype "bidirectional"))
      (node (ref "JP1") (pin "10") (pinfunction "10_10") (pintype "passive"))
      (node (ref "JP1") (pin "2") (pinfunction "2_2") (pintype "passive"))
      (node (ref "JP12") (pin "1") (pinfunction "1_1") (pintype "passive"))
      (node (ref "JP2") (pin "6") (pinfunction "6_6") (pintype "passive"))
      (node (ref "JP3") (pin "2") (pinfunction "2_2") (pintype "passive"))
      (node (ref "JP4") (pin "2") (pinfunction "2_2") (pintype "passive"))
      (node (ref "JP5") (pin "2") (pinfunction "2_2") (pintype "passive"))
      (node (ref "JP6") (pin "2") (pinfunction "2_2") (pintype "passive"))
      (node (ref "JP7") (pin "2") (pinfunction "2_2") (pintype "passive"))
      (node (ref "JP8") (pin "2") (pinfunction "2_2") (pintype "passive"))
      (node (ref "LED7") (pin "K") (pinfunction "C_K") (pintype "passive"))
      (node (ref "S1") (pin "1") (pinfunction "1_1") (pintype "passive"))
      (node (ref "S1") (pin "2") (pinfunction "2_2") (pintype "passive"))
    )
    (net (code "8") (name "JTAG-TCK") (class "Default")
      (node (ref "IC1") (pin "11") (pinfunction "PB6_11") (pintype "bidirectional"))
      (node (ref "JP1") (pin "1") (pinfunction "1_1") (pintype "passive"))
      (node (ref "R16") (pin "1") (pinfunction "1_1") (pintype "passive"))
    )
    (net (code "9") (name "JTAG-TDI") (class "Default")
      (node (ref "IC1") (pin "10") (pinfunction "PB5_10") (pintype "bidirectional"))
      (node (ref "JP1") (pin "9") (pinfunction "9_9") (pintype "passive"))
      (node (ref "R15") (pin "1") (pinfunction "1_1") (pintype "passive"))
    )
    (net (code "10") (name "JTAG-TDO") (class "Default")
      (node (ref "IC1") (pin "12") (pinfunction "PB7_12") (pintype "bidirectional"))
      (node (ref "JP1") (pin "3") (pinfunction "3_3") (pintype "passive"))
      (node (ref "R17") (pin "1") (pinfunction "1_1") (pintype "passive"))
    )
    (net (code "11") (name "JTAG-TMS") (class "Default")
      (node (ref "IC1") (pin "9") (pinfunction "PB4_9") (pintype "bidirectional"))
      (node (ref "JP1") (pin "5") (pinfunction "5_5") (pintype "passive"))
      (node (ref "R14") (pin "1") (pinfunction "1_1") (pintype "passive"))
    )
    (net (code "12") (name "Net-(C3-+)") (class "Default")
      (node (ref "C2") (pin "1") (pinfunction "1_1") (pintype "passive"))
      (node (ref "C3") (pin "A") (pinfunction "+_A") (pintype "passive"))
      (node (ref "IC4") (pin "20") (pinfunction "VCC_20") (pintype "power_in"))
      (node (ref "JP11") (pin "3") (pinfunction "3_3") (pintype "passive"))
      (node (ref "R22") (pin "2") (pinfunction "2_2") (pintype "passive"))
      (node (ref "R23") (pin "2") (pinfunction "2_2") (pintype "passive"))
    )
    (net (code "13") (name "Net-(C25-+)") (class "Default")
      (node (ref "C25") (pin "A") (pinfunction "+_A") (pintype "passive"))
      (node (ref "D1") (pin "C") (pinfunction "C_C") (pintype "passive"))
      (node (ref "IC3") (pin "3") (pinfunction "IN_3") (pintype "power_in"))
    )
    (net (code "14") (name "Net-(C32-+)") (class "Default")
      (node (ref "C32") (pin "A") (pinfunction "+_A") (pintype "passive"))
      (node (ref "C34") (pin "1") (pinfunction "1_1") (pintype "passive"))
      (node (ref "J5") (pin "4") (pinfunction "VDD_4") (pintype "bidirectional"))
      (node (ref "L2") (pin "2") (pinfunction "2_2") (pintype "passive"))
      (node (ref "R10") (pin "2") (pinfunction "2_2") (pintype "passive"))
      (node (ref "R11") (pin "2") (pinfunction "2_2") (pintype "passive"))
      (node (ref "R12") (pin "2") (pinfunction "2_2") (pintype "passive"))
      (node (ref "R13") (pin "2") (pinfunction "2_2") (pintype "passive"))
    )
    (net (code "15") (name "Net-(D1-PadA)") (class "Default")
      (node (ref "D1") (pin "A") (pinfunction "A_A") (pintype "passive"))
      (node (ref "J1") (pin "PWR") (pinfunction "PWR_PWR") (pintype "bidirectional"))
    )
    (net (code "16") (name "Net-(IC1-AVCC_A)") (class "Default")
      (node (ref "C6") (pin "1") (pinfunction "1_1") (pintype "passive"))
      (node (ref "IC1") (pin "4") (pinfunction "AVCC_B_4") (pintype "bidirectional"))
      (node (ref "IC1") (pin "94") (pinfunction "AVCC_A_94") (pintype "bidirectional"))
      (node (ref "L1") (pin "2") (pinfunction "2_2") (pintype "passive"))
    )
    (net (code "17") (name "Net-(IC1-PA0)") (class "Default")
      (node (ref "IC1") (pin "95") (pinfunction "PA0_95") (pintype "bidirectional"))
      (node (ref "JP3") (pin "9") (pinfunction "9_9") (pintype "passive"))
    )
    (net (code "18") (name "Net-(IC1-PA1)") (class "Default")
      (node (ref "IC1") (pin "96") (pinfunction "PA1_96") (pintype "bidirectional"))
      (node (ref "JP3") (pin "10") (pinfunction "10_10") (pintype "passive"))
    )
    (net (code "19") (name "Net-(IC1-PA2)") (class "Default")
      (node (ref "IC1") (pin "97") (pinfunction "PA2_97") (pintype "bidirectional"))
      (node (ref "JP4") (pin "3") (pinfunction "3_3") (pintype "passive"))
    )
    (net (code "20") (name "Net-(IC1-PA3)") (class "Default")
      (node (ref "IC1") (pin "98") (pinfunction "PA3_98") (pintype "bidirectional"))
      (node (ref "JP4") (pin "4") (pinfunction "4_4") (pintype "passive"))
    )
    (net (code "21") (name "Net-(IC1-PA4)") (class "Default")
      (node (ref "IC1") (pin "99") (pinfunction "PA4_99") (pintype "bidirectional"))
      (node (ref "JP4") (pin "5") (pinfunction "5_5") (pintype "passive"))
    )
    (net (code "22") (name "Net-(IC1-PA5)") (class "Default")
      (node (ref "IC1") (pin "100") (pinfunction "PA5_100") (pintype "bidirectional"))
      (node (ref "JP4") (pin "6") (pinfunction "6_6") (pintype "passive"))
    )
    (net (code "23") (name "Net-(IC1-PA6)") (class "Default")
      (node (ref "IC1") (pin "1") (pinfunction "PA6_1") (pintype "bidirectional"))
      (node (ref "JP4") (pin "7") (pinfunction "7_7") (pintype "passive"))
    )
    (net (code "24") (name "Net-(IC1-PA7)") (class "Default")
      (node (ref "IC1") (pin "2") (pinfunction "PA7_2") (pintype "bidirectional"))
      (node (ref "JP4") (pin "8") (pinfunction "8_8") (pintype "passive"))
    )
    (net (code "25") (name "Net-(IC1-PB0)") (class "Default")
      (node (ref "IC1") (pin "5") (pinfunction "PB0_5") (pintype "bidirectional"))
      (node (ref "JP5") (pin "4") (pinfunction "4_4") (pintype "passive"))
    )
    (net (code "26") (name "Net-(IC1-PB1)") (class "Default")
      (node (ref "IC1") (pin "6") (pinfunction "PB1_6") (pintype "bidirectional"))
      (node (ref "JP5") (pin "6") (pinfunction "6_6") (pintype "passive"))
    )
    (net (code "27") (name "Net-(IC1-PB2)") (class "Default")
      (node (ref "IC1") (pin "7") (pinfunction "PB2_7") (pintype "bidirectional"))
      (node (ref "JP3") (pin "3") (pinfunction "3_3") (pintype "passive"))
    )
    (net (code "28") (name "Net-(IC1-PB3)") (class "Default")
      (node (ref "IC1") (pin "8") (pinfunction "PB3_8") (pintype "bidirectional"))
      (node (ref "JP3") (pin "4") (pinfunction "4_4") (pintype "passive"))
    )
    (net (code "29") (name "Net-(IC1-PC2)") (class "Default")
      (node (ref "IC1") (pin "17") (pinfunction "PC2_17") (pintype "bidirectional"))
      (node (ref "IC4") (pin "1") (pinfunction "TXD_1") (pintype "output"))
    )
    (net (code "30") (name "Net-(IC1-PC3)") (class "Default")
      (node (ref "IC1") (pin "18") (pinfunction "PC3_18") (pintype "bidirectional"))
      (node (ref "IC4") (pin "5") (pinfunction "RXD_5") (pintype "input"))
    )
    (net (code "31") (name "Net-(IC1-PC4)") (class "Default")
      (node (ref "IC1") (pin "19") (pinfunction "PC4_19") (pintype "bidirectional"))
      (node (ref "IC8") (pin "1") (pinfunction "CS_1") (pintype "input"))
    )
    (net (code "32") (name "Net-(IC1-PC5)") (class "Default")
      (node (ref "IC1") (pin "20") (pinfunction "PC5_20") (pintype "bidirectional"))
      (node (ref "IC8") (pin "2") (pinfunction "DIN_2") (pintype "input"))
    )
    (net (code "33") (name "Net-(IC1-PC6)") (class "Default")
      (node (ref "IC1") (pin "21") (pinfunction "PC6_21") (pintype "bidirectional"))
      (node (ref "IC8") (pin "18") (pinfunction "DOUT_18") (pintype "output"))
    )
    (net (code "34") (name "Net-(IC1-PC7)") (class "Default")
      (node (ref "IC1") (pin "22") (pinfunction "PC7_22") (pintype "bidirectional"))
      (node (ref "IC8") (pin "20") (pinfunction "SCLK_20") (pintype "input"))
    )
    (net (code "35") (name "Net-(IC1-PD2)") (class "Default")
      (node (ref "IC1") (pin "27") (pinfunction "PD2_27") (pintype "bidirectional"))
      (node (ref "JP5") (pin "3") (pinfunction "3_3") (pintype "passive"))
    )
    (net (code "36") (name "Net-(IC1-PD3)") (class "Default")
      (node (ref "IC1") (pin "28") (pinfunction "PD3_28") (pintype "bidirectional"))
      (node (ref "JP5") (pin "5") (pinfunction "5_5") (pintype "passive"))
    )
    (net (code "37") (name "Net-(IC1-PD4)") (class "Default")
      (node (ref "IC1") (pin "29") (pinfunction "PD4_29") (pintype "bidirectional"))
      (node (ref "IC5") (pin "7") (pinfunction "SYNC_7") (pintype "input"))
    )
    (net (code "38") (name "Net-(IC1-PD5)") (class "Default")
      (node (ref "IC1") (pin "30") (pinfunction "PD5_30") (pintype "bidirectional"))
      (node (ref "IC5") (pin "9") (pinfunction "SDI_9") (pintype "input"))
    )
    (net (code "39") (name "Net-(IC1-PD6)") (class "Default")
      (node (ref "IC1") (pin "31") (pinfunction "PD6_31") (pintype "bidirectional"))
      (node (ref "IC5") (pin "16") (pinfunction "SDO_16") (pintype "output"))
    )
    (net (code "40") (name "Net-(IC1-PD7)") (class "Default")
      (node (ref "IC1") (pin "32") (pinfunction "PD7_32") (pintype "bidirectional"))
      (node (ref "IC5") (pin "8") (pinfunction "SCLK_8") (pintype "input"))
    )
    (net (code "41") (name "Net-(IC1-PE2)") (class "Default")
      (node (ref "IC1") (pin "37") (pinfunction "PE2_37") (pintype "bidirectional"))
      (node (ref "JP5") (pin "7") (pinfunction "7_7") (pintype "passive"))
    )
    (net (code "42") (name "Net-(IC1-PE3)") (class "Default")
      (node (ref "IC1") (pin "38") (pinfunction "PE3_38") (pintype "bidirectional"))
      (node (ref "JP5") (pin "9") (pinfunction "9_9") (pintype "passive"))
    )
    (net (code "43") (name "Net-(IC1-PE4)") (class "Default")
      (node (ref "IC1") (pin "39") (pinfunction "PE4_39") (pintype "bidirectional"))
      (node (ref "J5") (pin "1") (pinfunction "DAT3/CS_1") (pintype "bidirectional"))
    )
    (net (code "44") (name "Net-(IC1-PE5)") (class "Default")
      (node (ref "IC1") (pin "40") (pinfunction "PE5_40") (pintype "bidirectional"))
      (node (ref "J5") (pin "2") (pinfunction "CMD/DI_2") (pintype "bidirectional"))
    )
    (net (code "45") (name "Net-(IC1-PE6)") (class "Default")
      (node (ref "IC1") (pin "41") (pinfunction "PE6_41") (pintype "bidirectional"))
      (node (ref "J5") (pin "7") (pinfunction "DAT0/DO_7") (pintype "bidirectional"))
      (node (ref "R10") (pin "1") (pinfunction "1_1") (pintype "passive"))
    )
    (net (code "46") (name "Net-(IC1-PE7)") (class "Default")
      (node (ref "IC1") (pin "42") (pinfunction "PE7_42") (pintype "bidirectional"))
      (node (ref "J5") (pin "5") (pinfunction "CLK/SCLK_5") (pintype "bidirectional"))
    )
    (net (code "47") (name "Net-(IC1-PF2)") (class "Default")
      (node (ref "IC1") (pin "47") (pinfunction "PF2_47") (pintype "bidirectional"))
      (node (ref "JP5") (pin "11") (pinfunction "11_11") (pintype "passive"))
    )
    (net (code "48") (name "Net-(IC1-PF3)") (class "Default")
      (node (ref "IC1") (pin "48") (pinfunction "PF3_48") (pintype "bidirectional"))
      (node (ref "JP5") (pin "13") (pinfunction "13_13") (pintype "passive"))
    )
    (net (code "49") (name "Net-(IC1-PF4)") (class "Default")
      (node (ref "IC1") (pin "49") (pinfunction "PF4_49") (pintype "bidirectional"))
      (node (ref "JP5") (pin "8") (pinfunction "8_8") (pintype "passive"))
    )
    (net (code "50") (name "Net-(IC1-PF5)") (class "Default")
      (node (ref "IC1") (pin "50") (pinfunction "PF5_50") (pintype "bidirectional"))
      (node (ref "JP5") (pin "10") (pinfunction "10_10") (pintype "passive"))
    )
    (net (code "51") (name "Net-(IC1-PF6)") (class "Default")
      (node (ref "IC1") (pin "51") (pinfunction "PF6_51") (pintype "bidirectional"))
      (node (ref "JP5") (pin "12") (pinfunction "12_12") (pintype "passive"))
    )
    (net (code "52") (name "Net-(IC1-PF7)") (class "Default")
      (node (ref "IC1") (pin "52") (pinfunction "PF7_52") (pintype "bidirectional"))
      (node (ref "JP5") (pin "14") (pinfunction "14_14") (pintype "passive"))
    )
    (net (code "53") (name "Net-(IC1-PH0)") (class "Default")
      (node (ref "IC1") (pin "55") (pinfunction "PH0_55") (pintype "bidirectional"))
      (node (ref "J5") (pin "WP") (pinfunction "WP_WP") (pintype "bidirectional"))
      (node (ref "R12") (pin "1") (pinfunction "1_1") (pintype "passive"))
    )
    (net (code "54") (name "Net-(IC1-PH1)") (class "Default")
      (node (ref "IC1") (pin "56") (pinfunction "PH1_56") (pintype "bidirectional"))
      (node (ref "J5") (pin "CD") (pinfunction "CD_CD") (pintype "bidirectional"))
      (node (ref "R13") (pin "1") (pinfunction "1_1") (pintype "passive"))
    )
    (net (code "55") (name "Net-(IC1-PH2)") (class "Default")
      (node (ref "IC1") (pin "57") (pinfunction "PH2_57") (pintype "bidirectional"))
      (node (ref "JP5") (pin "15") (pinfunction "15_15") (pintype "passive"))
    )
    (net (code "56") (name "Net-(IC1-PH3)") (class "Default")
      (node (ref "IC1") (pin "58") (pinfunction "PH3_58") (pintype "bidirectional"))
      (node (ref "JP5") (pin "16") (pinfunction "16_16") (pintype "passive"))
    )
    (net (code "57") (name "Net-(IC1-PH4)") (class "Default")
      (node (ref "IC1") (pin "59") (pinfunction "PH4_59") (pintype "bidirectional"))
      (node (ref "JP5") (pin "17") (pinfunction "17_17") (pintype "passive"))
    )
    (net (code "58") (name "Net-(IC1-PH5)") (class "Default")
      (node (ref "IC1") (pin "60") (pinfunction "PH5_60") (pintype "bidirectional"))
      (node (ref "IC5") (pin "10") (pinfunction "LDAC_10") (pintype "input"))
    )
    (net (code "59") (name "Net-(IC1-PH6)") (class "Default")
      (node (ref "IC1") (pin "61") (pinfunction "PH6_61") (pintype "bidirectional"))
      (node (ref "IC5") (pin "11") (pinfunction "CLR_11") (pintype "input"))
    )
    (net (code "60") (name "Net-(IC1-PH7)") (class "Default")
      (node (ref "IC1") (pin "62") (pinfunction "PH7_62") (pintype "bidirectional"))
      (node (ref "IC5") (pin "5") (pinfunction "2SCOMP_5") (pintype "input"))
    )
    (net (code "61") (name "Net-(IC1-PJ0)") (class "Default")
      (node (ref "IC1") (pin "65") (pinfunction "PJ0_65") (pintype "bidirectional"))
      (node (ref "JP3") (pin "5") (pinfunction "5_5") (pintype "passive"))
    )
    (net (code "62") (name "Net-(IC1-PJ1)") (class "Default")
      (node (ref "IC1") (pin "66") (pinfunction "PJ1_66") (pintype "bidirectional"))
      (node (ref "JP3") (pin "6") (pinfunction "6_6") (pintype "passive"))
    )
    (net (code "63") (name "Net-(IC1-PJ2)") (class "Default")
      (node (ref "IC1") (pin "67") (pinfunction "PJ2_67") (pintype "bidirectional"))
      (node (ref "JP3") (pin "7") (pinfunction "7_7") (pintype "passive"))
    )
    (net (code "64") (name "Net-(IC1-PJ3)") (class "Default")
      (node (ref "IC1") (pin "68") (pinfunction "PJ3_68") (pintype "bidirectional"))
      (node (ref "JP3") (pin "8") (pinfunction "8_8") (pintype "passive"))
    )
    (net (code "65") (name "Net-(IC1-PJ4)") (class "Default")
      (node (ref "IC1") (pin "69") (pinfunction "PJ4_69") (pintype "bidirectional"))
      (node (ref "LED1") (pin "K") (pinfunction "C_K") (pintype "passive"))
    )
    (net (code "66") (name "Net-(IC1-PJ5)") (class "Default")
      (node (ref "IC1") (pin "70") (pinfunction "PJ5_70") (pintype "bidirectional"))
      (node (ref "LED2") (pin "K") (pinfunction "C_K") (pintype "passive"))
    )
    (net (code "67") (name "Net-(IC1-PJ6)") (class "Default")
      (node (ref "IC1") (pin "71") (pinfunction "PJ6_71") (pintype "bidirectional"))
      (node (ref "LED3") (pin "K") (pinfunction "C_K") (pintype "passive"))
    )
    (net (code "68") (name "Net-(IC1-PJ7)") (class "Default")
      (node (ref "IC1") (pin "72") (pinfunction "PJ7_72") (pintype "bidirectional"))
      (node (ref "LED4") (pin "K") (pinfunction "C_K") (pintype "passive"))
    )
    (net (code "69") (name "Net-(IC1-PK0)") (class "Default")
      (node (ref "IC1") (pin "75") (pinfunction "PK0_75") (pintype "bidirectional"))
      (node (ref "IC6") (pin "2") (pinfunction "B0_2") (pintype "input"))
      (node (ref "IC7") (pin "3") (pinfunction "O0_3") (pintype "output"))
    )
    (net (code "70") (name "Net-(IC1-PK1)") (class "Default")
      (node (ref "IC1") (pin "76") (pinfunction "PK1_76") (pintype "bidirectional"))
      (node (ref "IC6") (pin "5") (pinfunction "B1_5") (pintype "input"))
      (node (ref "IC7") (pin "6") (pinfunction "O1_6") (pintype "output"))
    )
    (net (code "71") (name "Net-(IC1-PK2)") (class "Default")
      (node (ref "IC1") (pin "77") (pinfunction "PK2_77") (pintype "bidirectional"))
      (node (ref "IC6") (pin "9") (pinfunction "B2_9") (pintype "input"))
      (node (ref "IC7") (pin "8") (pinfunction "O2_8") (pintype "output"))
    )
    (net (code "72") (name "Net-(IC1-PK3)") (class "Default")
      (node (ref "IC1") (pin "78") (pinfunction "PK3_78") (pintype "bidirectional"))
      (node (ref "IC6") (pin "12") (pinfunction "B3_12") (pintype "input"))
      (node (ref "IC7") (pin "11") (pinfunction "O3_11") (pintype "output"))
    )
    (net (code "73") (name "Net-(IC1-PK4)") (class "Default")
      (node (ref "IC1") (pin "79") (pinfunction "PK4_79") (pintype "bidirectional"))
      (node (ref "IC6") (pin "1") (pinfunction "A0_1") (pintype "input"))
      (node (ref "IC7") (pin "1") (pinfunction "A0_1") (pintype "input"))
    )
    (net (code "74") (name "Net-(IC1-PK5)") (class "Default")
      (node (ref "IC1") (pin "80") (pinfunction "PK5_80") (pintype "bidirectional"))
      (node (ref "IC6") (pin "4") (pinfunction "A1_4") (pintype "input"))
      (node (ref "IC7") (pin "4") (pinfunction "A1_4") (pintype "input"))
    )
    (net (code "75") (name "Net-(IC1-PK6)") (class "Default")
      (node (ref "IC1") (pin "81") (pinfunction "PK6_81") (pintype "bidirectional"))
      (node (ref "IC6") (pin "10") (pinfunction "A2_10") (pintype "input"))
      (node (ref "IC7") (pin "10") (pinfunction "A2_10") (pintype "input"))
    )
    (net (code "76") (name "Net-(IC1-PK7)") (class "Default")
      (node (ref "IC1") (pin "82") (pinfunction "PK7_82") (pintype "bidirectional"))
      (node (ref "IC6") (pin "13") (pinfunction "A3_13") (pintype "input"))
      (node (ref "IC7") (pin "13") (pinfunction "A3_13") (pintype "input"))
    )
    (net (code "77") (name "Net-(IC1-PR0)") (class "Default")
      (node (ref "C4") (pin "1") (pinfunction "1_1") (pintype "passive"))
      (node (ref "IC1") (pin "91") (pinfunction "PR0_91") (pintype "bidirectional"))
      (node (ref "Q1") (pin "1") (pinfunction "1_1") (pintype "passive"))
    )
    (net (code "78") (name "Net-(IC1-PR1)") (class "Default")
      (node (ref "C5") (pin "1") (pinfunction "1_1") (pintype "passive"))
      (node (ref "IC1") (pin "92") (pinfunction "PR1_92") (pintype "bidirectional"))
      (node (ref "Q1") (pin "2") (pinfunction "2_2") (pintype "passive"))
    )
    (net (code "79") (name "Net-(IC3-OUT)") (class "Default")
      (node (ref "IC3") (pin "2") (pinfunction "OUT_2") (pintype "power_in"))
      (node (ref "JP10") (pin "1") (pinfunction "1_1") (pintype "passive"))
    )
    (net (code "80") (name "Net-(IC4-3V3OUT)") (class "Default")
      (node (ref "C1") (pin "1") (pinfunction "1_1") (pintype "passive"))
      (node (ref "IC4") (pin "17") (pinfunction "3V3OUT_17") (pintype "output"))
      (node (ref "IC4") (pin "4") (pinfunction "VCCIO_4") (pintype "power_in"))
    )
    (net (code "81") (name "Net-(IC4-DTR)") (class "Default")
      (node (ref "C31") (pin "2") (pinfunction "2_2") (pintype "passive"))
      (node (ref "IC4") (pin "2") (pinfunction "DTR_2") (pintype "bidirectional"))
    )
    (net (code "82") (name "Net-(IC4-RXLED)") (class "Default")
      (node (ref "IC4") (pin "22") (pinfunction "RXLED_22") (pintype "bidirectional"))
      (node (ref "LED6") (pin "K") (pinfunction "C_K") (pintype "passive"))
    )
    (net (code "83") (name "Net-(IC4-TXLED)") (class "Default")
      (node (ref "IC4") (pin "23") (pinfunction "TXLED_23") (pintype "bidirectional"))
      (node (ref "LED5") (pin "K") (pinfunction "C_K") (pintype "passive"))
    )
    (net (code "84") (name "Net-(IC4-USBDM)") (class "Default")
      (node (ref "IC4") (pin "16") (pinfunction "USBDM_16") (pintype "bidirectional"))
      (node (ref "J3") (pin "D-") (pinfunction "D-_D-") (pintype "bidirectional"))
    )
    (net (code "85") (name "Net-(IC4-USBDP)") (class "Default")
      (node (ref "IC4") (pin "15") (pinfunction "USBDP_15") (pintype "bidirectional"))
      (node (ref "J3") (pin "D+") (pinfunction "D+_D+") (pintype "bidirectional"))
    )
    (net (code "86") (name "Net-(IC5-REF)") (class "Default")
      (node (ref "C17") (pin "1") (pinfunction "1_1") (pintype "passive"))
      (node (ref "IC5") (pin "17") (pinfunction "REF_17") (pintype "bidirectional"))
    )
    (net (code "87") (name "Net-(IC5-VOUTA)") (class "Default")
      (node (ref "IC5") (pin "3") (pinfunction "VOUTA_3") (pintype "output"))
      (node (ref "JP7") (pin "7") (pinfunction "7_7") (pintype "passive"))
    )
    (net (code "88") (name "Net-(IC5-VOUTB)") (class "Default")
      (node (ref "IC5") (pin "4") (pinfunction "VOUTB_4") (pintype "output"))
      (node (ref "JP7") (pin "8") (pinfunction "8_8") (pintype "passive"))
    )
    (net (code "89") (name "Net-(IC5-VOUTC)") (class "Default")
      (node (ref "IC5") (pin "23") (pinfunction "VOUTC_23") (pintype "output"))
      (node (ref "JP6") (pin "3") (pinfunction "3_3") (pintype "passive"))
    )
    (net (code "90") (name "Net-(IC5-VOUTD)") (class "Default")
      (node (ref "IC5") (pin "22") (pinfunction "VOUTD_22") (pintype "output"))
      (node (ref "JP6") (pin "4") (pinfunction "4_4") (pintype "passive"))
    )
    (net (code "91") (name "Net-(IC6-O0)") (class "Default")
      (node (ref "IC6") (pin "3") (pinfunction "O0_3") (pintype "output"))
      (node (ref "IC7") (pin "2") (pinfunction "B0_2") (pintype "input"))
      (node (ref "JP6") (pin "5") (pinfunction "5_5") (pintype "passive"))
    )
    (net (code "92") (name "Net-(IC6-O1)") (class "Default")
      (node (ref "IC6") (pin "6") (pinfunction "O1_6") (pintype "output"))
      (node (ref "IC7") (pin "5") (pinfunction "B1_5") (pintype "input"))
      (node (ref "JP6") (pin "6") (pinfunction "6_6") (pintype "passive"))
    )
    (net (code "93") (name "Net-(IC6-O2)") (class "Default")
      (node (ref "IC6") (pin "8") (pinfunction "O2_8") (pintype "output"))
      (node (ref "IC7") (pin "9") (pinfunction "B2_9") (pintype "input"))
      (node (ref "JP6") (pin "7") (pinfunction "7_7") (pintype "passive"))
    )
    (net (code "94") (name "Net-(IC6-O3)") (class "Default")
      (node (ref "IC6") (pin "11") (pinfunction "O3_11") (pintype "output"))
      (node (ref "IC7") (pin "12") (pinfunction "B3_12") (pintype "input"))
      (node (ref "JP6") (pin "8") (pinfunction "8_8") (pintype "passive"))
    )
    (net (code "95") (name "Net-(IC8-VIN0)") (class "Default")
      (node (ref "IC8") (pin "7") (pinfunction "VIN0_7") (pintype "input"))
      (node (ref "JP6") (pin "9") (pinfunction "9_9") (pintype "passive"))
    )
    (net (code "96") (name "Net-(IC8-VIN1)") (class "Default")
      (node (ref "IC8") (pin "8") (pinfunction "VIN1_8") (pintype "input"))
      (node (ref "JP6") (pin "10") (pinfunction "10_10") (pintype "passive"))
    )
    (net (code "97") (name "Net-(IC8-VIN2)") (class "Default")
      (node (ref "IC8") (pin "14") (pinfunction "VIN2_14") (pintype "input"))
      (node (ref "JP7") (pin "3") (pinfunction "3_3") (pintype "passive"))
    )
    (net (code "98") (name "Net-(IC8-VIN3)") (class "Default")
      (node (ref "IC8") (pin "13") (pinfunction "VIN3_13") (pintype "input"))
      (node (ref "JP7") (pin "4") (pinfunction "4_4") (pintype "passive"))
    )
    (net (code "99") (name "Net-(IC8-VIN4)") (class "Default")
      (node (ref "IC8") (pin "9") (pinfunction "VIN4_9") (pintype "input"))
      (node (ref "JP7") (pin "5") (pinfunction "5_5") (pintype "passive"))
    )
    (net (code "100") (name "Net-(IC8-VIN5)") (class "Default")
      (node (ref "IC8") (pin "10") (pinfunction "VIN5_10") (pintype "input"))
      (node (ref "JP7") (pin "6") (pinfunction "6_6") (pintype "passive"))
    )
    (net (code "101") (name "Net-(IC8-VIN6)") (class "Default")
      (node (ref "IC8") (pin "12") (pinfunction "VIN6_12") (pintype "input"))
      (node (ref "JP8") (pin "3") (pinfunction "3_3") (pintype "passive"))
    )
    (net (code "102") (name "Net-(IC8-VIN7)") (class "Default")
      (node (ref "IC8") (pin "11") (pinfunction "VIN7_11") (pintype "input"))
      (node (ref "JP8") (pin "4") (pinfunction "4_4") (pintype "passive"))
    )
    (net (code "103") (name "Net-(IC8-VREF)") (class "Default")
      (node (ref "C24") (pin "1") (pinfunction "1_1") (pintype "passive"))
      (node (ref "IC8") (pin "5") (pinfunction "VREF_5") (pintype "power_in"))
    )
    (net (code "104") (name "Net-(IC11B-LX)") (class "Default")
      (node (ref "IC11") (pin "2") (pinfunction "LX_2") (pintype "bidirectional"))
      (node (ref "J4") (pin "1") (pinfunction "1_1") (pintype "passive"))
      (node (ref "R26") (pin "1") (pinfunction "1_1") (pintype "passive"))
    )
    (net (code "105") (name "Net-(IC11B-LY)") (class "Default")
      (node (ref "IC11") (pin "7") (pinfunction "LY_7") (pintype "bidirectional"))
      (node (ref "J4") (pin "6") (pinfunction "6_6") (pintype "passive"))
      (node (ref "R27") (pin "1") (pinfunction "1_1") (pintype "passive"))
    )
    (net (code "106") (name "Net-(IC12B-LX)") (class "Default")
      (node (ref "IC12") (pin "2") (pinfunction "LX_2") (pintype "bidirectional"))
      (node (ref "J4") (pin "2") (pinfunction "2_2") (pintype "passive"))
      (node (ref "R28") (pin "1") (pinfunction "1_1") (pintype "passive"))
    )
    (net (code "107") (name "Net-(IC12B-LY)") (class "Default")
      (node (ref "IC12") (pin "7") (pinfunction "LY_7") (pintype "bidirectional"))
      (node (ref "J4") (pin "7") (pinfunction "7_7") (pintype "passive"))
      (node (ref "R29") (pin "1") (pinfunction "1_1") (pintype "passive"))
    )
    (net (code "108") (name "Net-(IC13B-LX)") (class "Default")
      (node (ref "IC13") (pin "2") (pinfunction "LX_2") (pintype "bidirectional"))
      (node (ref "J4") (pin "3") (pinfunction "3_3") (pintype "passive"))
      (node (ref "R30") (pin "1") (pinfunction "1_1") (pintype "passive"))
    )
    (net (code "109") (name "Net-(IC13B-LY)") (class "Default")
      (node (ref "IC13") (pin "7") (pinfunction "LY_7") (pintype "bidirectional"))
      (node (ref "J4") (pin "8") (pinfunction "8_8") (pintype "passive"))
      (node (ref "R31") (pin "1") (pinfunction "1_1") (pintype "passive"))
    )
    (net (code "110") (name "Net-(IC14B-LX)") (class "Default")
      (node (ref "IC14") (pin "2") (pinfunction "LX_2") (pintype "bidirectional"))
      (node (ref "J4") (pin "4") (pinfunction "4_4") (pintype "passive"))
      (node (ref "R32") (pin "1") (pinfunction "1_1") (pintype "passive"))
    )
    (net (code "111") (name "Net-(IC14B-LY)") (class "Default")
      (node (ref "IC14") (pin "7") (pinfunction "LY_7") (pintype "bidirectional"))
      (node (ref "J4") (pin "9") (pinfunction "9_9") (pintype "passive"))
      (node (ref "R33") (pin "1") (pinfunction "1_1") (pintype "passive"))
    )
    (net (code "112") (name "Net-(IC15-EN)") (class "Default")
      (node (ref "IC15") (pin "1") (pinfunction "EN_1") (pintype "bidirectional"))
      (node (ref "R25") (pin "1") (pinfunction "1_1") (pintype "passive"))
    )
    (net (code "113") (name "Net-(J3-PadVBUS)") (class "Default")
      (node (ref "J3") (pin "VBUS") (pinfunction "VBUS_VBUS") (pintype "bidirectional"))
      (node (ref "JP11") (pin "2") (pinfunction "2_2") (pintype "passive"))
    )
    (net (code "114") (name "Net-(J5-DAT1)") (class "Default")
      (node (ref "J5") (pin "8") (pinfunction "DAT1_8") (pintype "bidirectional"))
      (node (ref "J5") (pin "9") (pinfunction "DAT2_9") (pintype "bidirectional"))
      (node (ref "R11") (pin "1") (pinfunction "1_1") (pintype "passive"))
    )
    (net (code "115") (name "Net-(LED1-PadA)") (class "Default")
      (node (ref "LED1") (pin "A") (pinfunction "A_A") (pintype "passive"))
      (node (ref "R18") (pin "1") (pinfunction "1_1") (pintype "passive"))
    )
    (net (code "116") (name "Net-(LED2-PadA)") (class "Default")
      (node (ref "LED2") (pin "A") (pinfunction "A_A") (pintype "passive"))
      (node (ref "R19") (pin "1") (pinfunction "1_1") (pintype "passive"))
    )
    (net (code "117") (name "Net-(LED3-PadA)") (class "Default")
      (node (ref "LED3") (pin "A") (pinfunction "A_A") (pintype "passive"))
      (node (ref "R20") (pin "1") (pinfunction "1_1") (pintype "passive"))
    )
    (net (code "118") (name "Net-(LED4-PadA)") (class "Default")
      (node (ref "LED4") (pin "A") (pinfunction "A_A") (pintype "passive"))
      (node (ref "R21") (pin "1") (pinfunction "1_1") (pintype "passive"))
    )
    (net (code "119") (name "Net-(LED5-PadA)") (class "Default")
      (node (ref "LED5") (pin "A") (pinfunction "A_A") (pintype "passive"))
      (node (ref "R22") (pin "1") (pinfunction "1_1") (pintype "passive"))
    )
    (net (code "120") (name "Net-(LED6-PadA)") (class "Default")
      (node (ref "LED6") (pin "A") (pinfunction "A_A") (pintype "passive"))
      (node (ref "R23") (pin "1") (pinfunction "1_1") (pintype "passive"))
    )
    (net (code "121") (name "Net-(LED7-PadA)") (class "Default")
      (node (ref "LED7") (pin "A") (pinfunction "A_A") (pintype "passive"))
      (node (ref "R24") (pin "1") (pinfunction "1_1") (pintype "passive"))
    )
    (net (code "122") (name "PDI-DATA") (class "Default")
      (node (ref "IC1") (pin "89") (pinfunction "PDI_DATA_89") (pintype "bidirectional"))
      (node (ref "JP2") (pin "1") (pinfunction "1_1") (pintype "passive"))
    )
    (net (code "123") (name "RESET") (class "Default")
      (node (ref "C31") (pin "1") (pinfunction "1_1") (pintype "passive"))
      (node (ref "IC1") (pin "90") (pinfunction "RESET_90") (pintype "bidirectional"))
      (node (ref "JP1") (pin "6") (pinfunction "6_6") (pintype "passive"))
      (node (ref "JP2") (pin "5") (pinfunction "5_5") (pintype "passive"))
      (node (ref "R9") (pin "1") (pinfunction "1_1") (pintype "passive"))
      (node (ref "S1") (pin "3") (pinfunction "3_3") (pintype "passive"))
      (node (ref "S1") (pin "4") (pinfunction "4_4") (pintype "passive"))
    )
    (net (code "124") (name "SCL0") (class "Default")
      (node (ref "IC11") (pin "6") (pinfunction "SY_6") (pintype "bidirectional"))
      (node (ref "IC15") (pin "8") (pinfunction "B7_8") (pintype "bidirectional"))
      (node (ref "JP7") (pin "9") (pinfunction "9_9") (pintype "passive"))
      (node (ref "R2") (pin "1") (pinfunction "1_1") (pintype "passive"))
    )
    (net (code "125") (name "SCL0-3.3") (class "Default")
      (node (ref "IC1") (pin "16") (pinfunction "PC1_16") (pintype "bidirectional"))
      (node (ref "IC15") (pin "13") (pinfunction "A7_13") (pintype "bidirectional"))
    )
    (net (code "126") (name "SCL1") (class "Default")
      (node (ref "IC11") (pin "3") (pinfunction "SX_3") (pintype "bidirectional"))
      (node (ref "IC15") (pin "9") (pinfunction "B8_9") (pintype "bidirectional"))
      (node (ref "JP4") (pin "9") (pinfunction "9_9") (pintype "passive"))
      (node (ref "R1") (pin "1") (pinfunction "1_1") (pintype "passive"))
    )
    (net (code "127") (name "SCL1-3.3") (class "Default")
      (node (ref "IC1") (pin "26") (pinfunction "PD1_26") (pintype "bidirectional"))
      (node (ref "IC15") (pin "12") (pinfunction "A8_12") (pintype "bidirectional"))
    )
    (net (code "128") (name "SCL2") (class "Default")
      (node (ref "IC13") (pin "3") (pinfunction "SX_3") (pintype "bidirectional"))
      (node (ref "IC15") (pin "5") (pinfunction "B4_5") (pintype "bidirectional"))
      (node (ref "R5") (pin "1") (pinfunction "1_1") (pintype "passive"))
    )
    (net (code "129") (name "SCL2-3.3") (class "Default")
      (node (ref "IC1") (pin "36") (pinfunction "PE1_36") (pintype "bidirectional"))
      (node (ref "IC15") (pin "16") (pinfunction "A4_16") (pintype "bidirectional"))
    )
    (net (code "130") (name "SCL3") (class "Default")
      (node (ref "IC12") (pin "6") (pinfunction "SY_6") (pintype "bidirectional"))
      (node (ref "IC15") (pin "6") (pinfunction "B5_6") (pintype "bidirectional"))
      (node (ref "R4") (pin "1") (pinfunction "1_1") (pintype "passive"))
    )
    (net (code "131") (name "SCL3-3.3") (class "Default")
      (node (ref "IC1") (pin "46") (pinfunction "PF1_46") (pintype "bidirectional"))
      (node (ref "IC15") (pin "15") (pinfunction "A5_15") (pintype "bidirectional"))
    )
    (net (code "132") (name "SDA0") (class "Default")
      (node (ref "IC13") (pin "6") (pinfunction "SY_6") (pintype "bidirectional"))
      (node (ref "IC15") (pin "4") (pinfunction "B3_4") (pintype "bidirectional"))
      (node (ref "JP7") (pin "10") (pinfunction "10_10") (pintype "passive"))
      (node (ref "R6") (pin "1") (pinfunction "1_1") (pintype "passive"))
    )
    (net (code "133") (name "SDA0-3.3") (class "Default")
      (node (ref "IC1") (pin "15") (pinfunction "PC0_15") (pintype "bidirectional"))
      (node (ref "IC15") (pin "17") (pinfunction "A3_17") (pintype "bidirectional"))
    )
    (net (code "134") (name "SDA1") (class "Default")
      (node (ref "IC12") (pin "3") (pinfunction "SX_3") (pintype "bidirectional"))
      (node (ref "IC15") (pin "7") (pinfunction "B6_7") (pintype "bidirectional"))
      (node (ref "JP4") (pin "10") (pinfunction "10_10") (pintype "passive"))
      (node (ref "R3") (pin "1") (pinfunction "1_1") (pintype "passive"))
    )
    (net (code "135") (name "SDA1-3.3") (class "Default")
      (node (ref "IC1") (pin "25") (pinfunction "PD0_25") (pintype "bidirectional"))
      (node (ref "IC15") (pin "14") (pinfunction "A6_14") (pintype "bidirectional"))
    )
    (net (code "136") (name "SDA2") (class "Default")
      (node (ref "IC14") (pin "3") (pinfunction "SX_3") (pintype "bidirectional"))
      (node (ref "IC15") (pin "3") (pinfunction "B2_3") (pintype "bidirectional"))
      (node (ref "R7") (pin "1") (pinfunction "1_1") (pintype "passive"))
    )
    (net (code "137") (name "SDA2-3.3") (class "Default")
      (node (ref "IC1") (pin "35") (pinfunction "PE0_35") (pintype "bidirectional"))
      (node (ref "IC15") (pin "18") (pinfunction "A2_18") (pintype "bidirectional"))
    )
    (net (code "138") (name "SDA3") (class "Default")
      (node (ref "IC14") (pin "6") (pinfunction "SY_6") (pintype "bidirectional"))
      (node (ref "IC15") (pin "2") (pinfunction "B1_2") (pintype "bidirectional"))
      (node (ref "R8") (pin "1") (pinfunction "1_1") (pintype "passive"))
    )
    (net (code "139") (name "SDA3-3.3") (class "Default")
      (node (ref "IC1") (pin "45") (pinfunction "PF0_45") (pintype "bidirectional"))
      (node (ref "IC15") (pin "19") (pinfunction "A1_19") (pintype "bidirectional"))
    )
    (net (code "140") (name "unconnected-(IC1-PQ0-Pad85)") (class "Default")
      (node (ref "IC1") (pin "85") (pinfunction "PQ0_85") (pintype "bidirectional"))
    )
    (net (code "141") (name "unconnected-(IC1-PQ1-Pad86)") (class "Default")
      (node (ref "IC1") (pin "86") (pinfunction "PQ1_86") (pintype "bidirectional"))
    )
    (net (code "142") (name "unconnected-(IC1-PQ2-Pad87)") (class "Default")
      (node (ref "IC1") (pin "87") (pinfunction "PQ2_87") (pintype "bidirectional"))
    )
    (net (code "143") (name "unconnected-(IC1-PQ3-Pad88)") (class "Default")
      (node (ref "IC1") (pin "88") (pinfunction "PQ3_88") (pintype "bidirectional"))
    )
    (net (code "144") (name "unconnected-(IC4-CTS-Pad11)") (class "Default")
      (node (ref "IC4") (pin "11") (pinfunction "CTS_11") (pintype "bidirectional"))
    )
    (net (code "145") (name "unconnected-(IC4-RTS-Pad3)") (class "Default")
      (node (ref "IC4") (pin "3") (pinfunction "RTS_3") (pintype "bidirectional"))
    )
    (net (code "146") (name "unconnected-(J1-PadGNDBREAK)") (class "Default")
      (node (ref "J1") (pin "GNDBREAK") (pinfunction "GNDBREAK_GNDBREAK") (pintype "bidirectional"))
    )
    (net (code "147") (name "unconnected-(JP1-Pad7)") (class "Default")
      (node (ref "JP1") (pin "7") (pinfunction "7_7") (pintype "passive"))
    )
    (net (code "148") (name "unconnected-(JP1-Pad8)") (class "Default")
      (node (ref "JP1") (pin "8") (pinfunction "8_8") (pintype "passive"))
    )
    (net (code "149") (name "unconnected-(JP2-Pad3)") (class "Default")
      (node (ref "JP2") (pin "3") (pinfunction "3_3") (pintype "passive"))
    )
    (net (code "150") (name "unconnected-(JP2-Pad4)") (class "Default")
      (node (ref "JP2") (pin "4") (pinfunction "4_4") (pintype "passive"))
    )
    (net (code "151") (name "unconnected-(JP8-Pad5)") (class "Default")
      (node (ref "JP8") (pin "5") (pinfunction "5_5") (pintype "passive"))
    )
    (net (code "152") (name "unconnected-(JP8-Pad6)") (class "Default")
      (node (ref "JP8") (pin "6") (pinfunction "6_6") (pintype "passive"))
    )
    (net (code "153") (name "unconnected-(JP8-Pad7)") (class "Default")
      (node (ref "JP8") (pin "7") (pinfunction "7_7") (pintype "passive"))
    )
    (net (code "154") (name "unconnected-(JP8-Pad8)") (class "Default")
      (node (ref "JP8") (pin "8") (pinfunction "8_8") (pintype "passive"))
    )
    (net (code "155") (name "unconnected-(JP8-Pad9)") (class "Default")
      (node (ref "JP8") (pin "9") (pinfunction "9_9") (pintype "passive"))
    )
    (net (code "156") (name "unconnected-(JP8-Pad10)") (class "Default")
      (node (ref "JP8") (pin "10") (pinfunction "10_10") (pintype "passive"))
    )
  )
)
